# CPU.net
KiCad netlist of a schematic drawn in Altium Designer
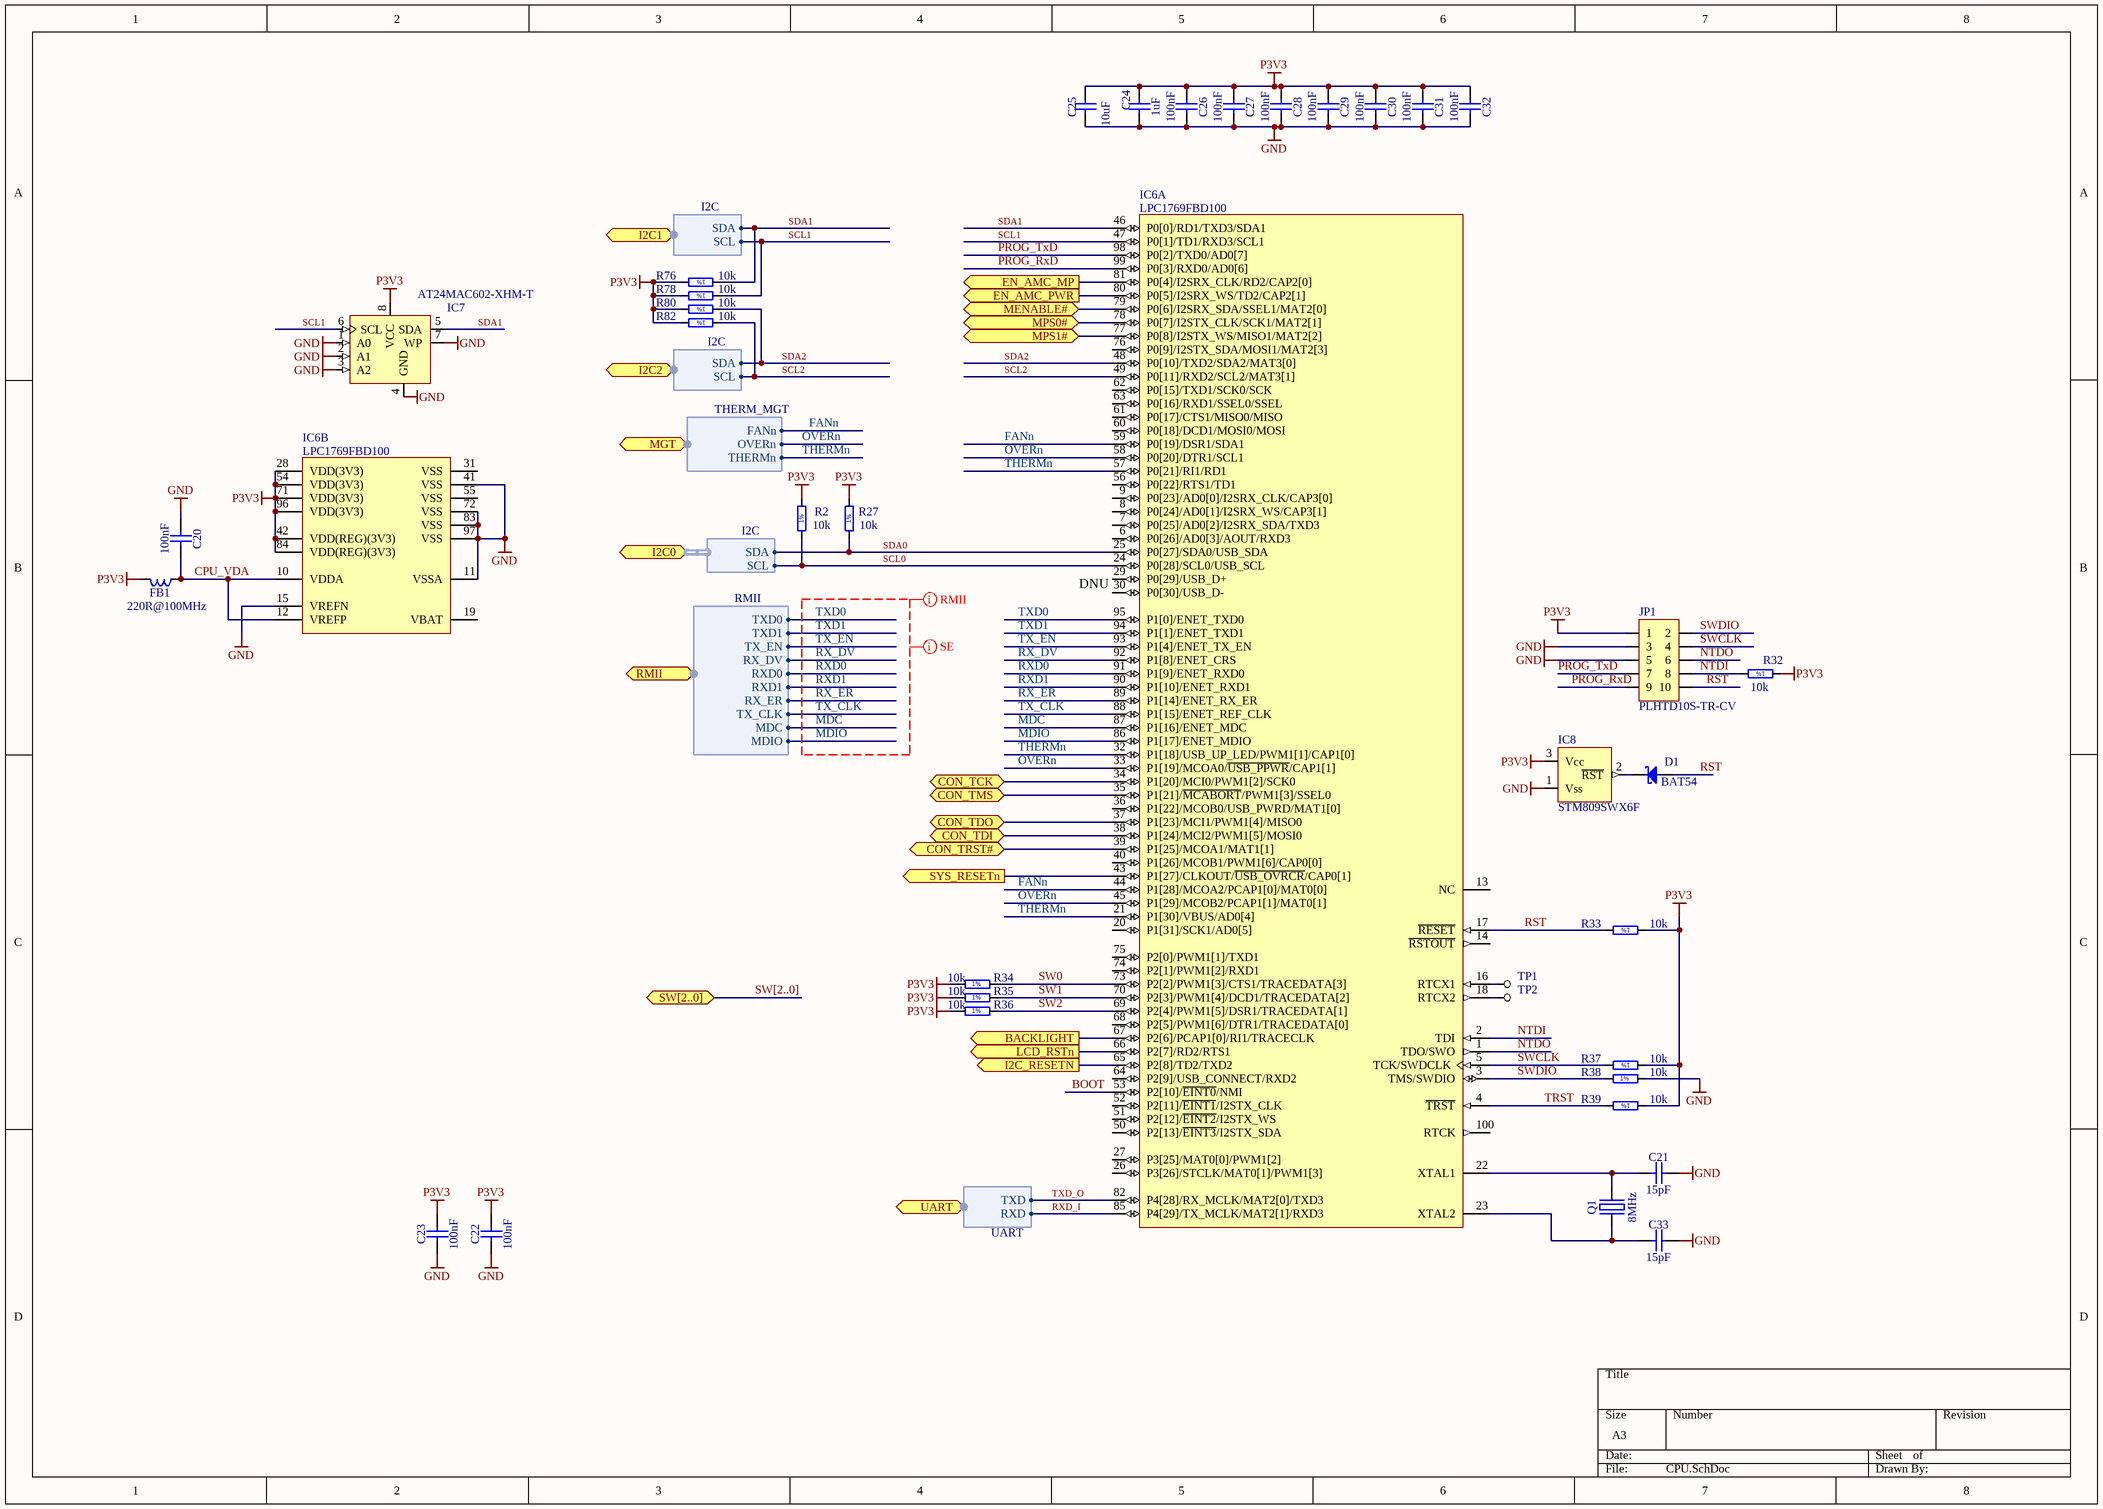
[diagram p0: CPU.SchDoc]

(export (version "E")
  (design (tool "Eeschema 10.0.6"))
  (components
    (comp (ref "C20")
      (value "100nF")
      (footprint "CAPC1005X55N")
      (description "Non-polarised capacitor")
      (fields
        (field (name "PART NUMBER") "CC0402_100NF_16V_10%_X5R")
        (field (name "VOLTAGE") "16V")
        (field (name "AUTHOR") "CERN DEM JLC")
      )
      (libsource (lib "Capacitors") (part "Capacitor - non polarized"))
    )
    (comp (ref "C21")
      (value "15pF")
      (footprint "CAPC1005X55N")
      (description "Non-polarised capacitor")
      (fields
        (field (name "PART NUMBER") "CC0402_15PF_50V_5%_C0G")
        (field (name "VOLTAGE") "50V")
        (field (name "AUTHOR") "CERN DEM JLC")
      )
      (libsource (lib "Capacitors") (part "Capacitor - non polarized"))
    )
    (comp (ref "C22")
      (value "100nF")
      (footprint "CAPC1005X55N")
      (description "Non-polarised capacitor")
      (fields
        (field (name "PART NUMBER") "CC0402_100NF_16V_10%_X5R")
        (field (name "VOLTAGE") "16V")
        (field (name "AUTHOR") "CERN DEM JLC")
      )
      (libsource (lib "Capacitors") (part "Capacitor - non polarized"))
    )
    (comp (ref "C23")
      (value "100nF")
      (footprint "CAPC1005X55N")
      (description "Non-polarised capacitor")
      (fields
        (field (name "PART NUMBER") "CC0402_100NF_16V_10%_X5R")
        (field (name "VOLTAGE") "16V")
        (field (name "AUTHOR") "CERN DEM JLC")
      )
      (libsource (lib "Capacitors") (part "Capacitor - non polarized"))
    )
    (comp (ref "C24")
      (value "1uF")
      (footprint "CAPC1608X87N")
      (description "Non-polarised capacitor")
      (fields
        (field (name "PART NUMBER") "CC0603_1UF_25V_10%_X7R")
        (field (name "VOLTAGE") "25V")
        (field (name "AUTHOR") "CERN DEM JLC")
      )
      (libsource (lib "Capacitors") (part "Capacitor - non polarized"))
    )
    (comp (ref "C25")
      (value "10uF")
      (footprint "CAPC2012X135N")
      (description "Non-polarised capacitor")
      (fields
        (field (name "PART NUMBER") "CC0805_10UF_10V_10%_X7R")
        (field (name "VOLTAGE") "10V")
        (field (name "AUTHOR") "CERN DEM JLC")
      )
      (libsource (lib "Capacitors") (part "Capacitor - non polarized"))
    )
    (comp (ref "C26")
      (value "100nF")
      (footprint "CAPC1005X55N")
      (description "Non-polarised capacitor")
      (fields
        (field (name "PART NUMBER") "CC0402_100NF_16V_10%_X5R")
        (field (name "VOLTAGE") "16V")
        (field (name "AUTHOR") "CERN DEM JLC")
      )
      (libsource (lib "Capacitors") (part "Capacitor - non polarized"))
    )
    (comp (ref "C27")
      (value "100nF")
      (footprint "CAPC1005X55N")
      (description "Non-polarised capacitor")
      (fields
        (field (name "PART NUMBER") "CC0402_100NF_16V_10%_X5R")
        (field (name "VOLTAGE") "16V")
        (field (name "AUTHOR") "CERN DEM JLC")
      )
      (libsource (lib "Capacitors") (part "Capacitor - non polarized"))
    )
    (comp (ref "C28")
      (value "100nF")
      (footprint "CAPC1005X55N")
      (description "Non-polarised capacitor")
      (fields
        (field (name "PART NUMBER") "CC0402_100NF_16V_10%_X5R")
        (field (name "VOLTAGE") "16V")
        (field (name "AUTHOR") "CERN DEM JLC")
      )
      (libsource (lib "Capacitors") (part "Capacitor - non polarized"))
    )
    (comp (ref "C29")
      (value "100nF")
      (footprint "CAPC1005X55N")
      (description "Non-polarised capacitor")
      (fields
        (field (name "PART NUMBER") "CC0402_100NF_16V_10%_X5R")
        (field (name "VOLTAGE") "16V")
        (field (name "AUTHOR") "CERN DEM JLC")
      )
      (libsource (lib "Capacitors") (part "Capacitor - non polarized"))
    )
    (comp (ref "C30")
      (value "100nF")
      (footprint "CAPC1005X55N")
      (description "Non-polarised capacitor")
      (fields
        (field (name "PART NUMBER") "CC0402_100NF_16V_10%_X5R")
        (field (name "VOLTAGE") "16V")
        (field (name "AUTHOR") "CERN DEM JLC")
      )
      (libsource (lib "Capacitors") (part "Capacitor - non polarized"))
    )
    (comp (ref "C31")
      (value "100nF")
      (footprint "CAPC1005X55N")
      (description "Non-polarised capacitor")
      (fields
        (field (name "PART NUMBER") "CC0402_100NF_16V_10%_X5R")
        (field (name "VOLTAGE") "16V")
        (field (name "AUTHOR") "CERN DEM JLC")
      )
      (libsource (lib "Capacitors") (part "Capacitor - non polarized"))
    )
    (comp (ref "C32")
      (value "100nF")
      (footprint "CAPC1005X55N")
      (description "Non-polarised capacitor")
      (fields
        (field (name "PART NUMBER") "CC0402_100NF_16V_10%_X5R")
        (field (name "VOLTAGE") "16V")
        (field (name "AUTHOR") "CERN DEM JLC")
      )
      (libsource (lib "Capacitors") (part "Capacitor - non polarized"))
    )
    (comp (ref "C33")
      (value "15pF")
      (footprint "CAPC1005X55N")
      (description "Non-polarised capacitor")
      (fields
        (field (name "PART NUMBER") "CC0402_15PF_50V_5%_C0G")
        (field (name "VOLTAGE") "50V")
        (field (name "AUTHOR") "CERN DEM JLC")
      )
      (libsource (lib "Capacitors") (part "Capacitor - non polarized"))
    )
    (comp (ref "D1")
      (value "BAT54")
      (footprint "SOT95P240X130-3N")
      (description "Diode Schottky  Anode Pin 1 Cathode Pin 3 (Pas de pin 2)")
      (fields
        (field (name "VOLTAGE") "30V")
        (field (name "POWER") "200mA")
        (field (name "AUTHOR") "CERN DEM JLC")
      )
      (libsource (lib "ICs And Semiconductors") (part "Diode Schottky A1C3"))
    )
    (comp (ref "FB1")
      (value "220R@100MHz")
      (footprint "INDC2012X105N")
      (description "Inductor")
      (fields
        (field (name "PART NUMBER") "IND0805_MURATA_BLM21PG221SN1D")
        (field (name "POWER") "2A")
        (field (name "AUTHOR") "CERN DEM JLC")
      )
      (libsource (lib "Inductors & Transformers") (part "Inductor"))
    )
    (comp (ref "IC6")
      (value "LPC1769FBD100")
      (footprint "QFP50P1600X1600X160-100N")
      (description "LPC1768 Series 64kB 120MHz 32-Bit ARM Cortex-M3 Microcontroller")
      (fields (field (name "MANUFACTURER") "NXP SEMICONDUCTORS") (field (name "AUTHOR") "CERN DEM JLC"))
      (libsource (lib "ICs And Semiconductors") (part "LPC1769FBD100"))
    )
    (comp (ref "IC7")
      (value "AT24MAC602-XHM-T")
      (footprint "TSSOP-8")
      (description "Serial 2K EEPROM+ 48bit MAC")
      (libsource (lib "LIBRARY_SCH") (part "MEM_24MAC602"))
    )
    (comp (ref "IC8")
      (value "STM809SWX6F")
      (footprint "SOT-23")
      (description "2.93V  Reset circuit")
      (libsource (lib "LIBRARY_SCH") (part "VMON_STM809"))
    )
    (comp (ref "JP1")
      (value "PLHTD10S-TR-CV")
      (footprint "PLHTD10S-TR-CV")
      (description "1.27 mm dual row goldpin (Maritex)")
      (libsource (lib "LIBRARY_SCH") (part "CON_2x5 1.27 SMT Male"))
    )
    (comp (ref "Q1")
      (value "8MHz")
      (footprint "XTAL_TXC_7A")
      (description "Quartz Crystal")
      (fields
        (field (name "PART NUMBER") "XTAL_8MHZ_TXC_7A-8.000MAAE-T")
        (field (name "MANUFACTURER") "TXC CORPORATION")
        (field (name "AUTHOR") "CERN DEM JLC")
      )
      (libsource (lib "ICs And Semiconductors") (part "Quartz Crystal"))
    )
    (comp (ref "R2")
      (value "10k")
      (footprint "RESC1005X40N")
      (description "Resistor - 1%")
      (fields
        (field (name "PART NUMBER") "R0402_10K_1%_0.0625W_100PPM")
        (field (name "POWER") "0.0625W")
        (field (name "AUTHOR") "CERN DEM JLC")
      )
      (libsource (lib "Resistors") (part "Resistor - 1%"))
    )
    (comp (ref "R27")
      (value "10k")
      (footprint "RESC1005X40N")
      (description "Resistor - 1%")
      (fields
        (field (name "PART NUMBER") "R0402_10K_1%_0.0625W_100PPM")
        (field (name "POWER") "0.0625W")
        (field (name "AUTHOR") "CERN DEM JLC")
      )
      (libsource (lib "Resistors") (part "Resistor - 1%"))
    )
    (comp (ref "R32")
      (value "10k")
      (footprint "RESC1005X40N")
      (description "Resistor - 1%")
      (fields
        (field (name "PART NUMBER") "R0402_10K_1%_0.0625W_100PPM")
        (field (name "POWER") "0.0625W")
        (field (name "AUTHOR") "CERN DEM JLC")
      )
      (libsource (lib "Resistors") (part "Resistor - 1%"))
    )
    (comp (ref "R33")
      (value "10k")
      (footprint "RESC1005X40N")
      (description "Resistor - 1%")
      (fields
        (field (name "PART NUMBER") "R0402_10K_1%_0.0625W_100PPM")
        (field (name "POWER") "0.0625W")
        (field (name "AUTHOR") "CERN DEM JLC")
      )
      (libsource (lib "Resistors") (part "Resistor - 1%"))
    )
    (comp (ref "R34")
      (value "10k")
      (footprint "RESC1005X40N")
      (description "Resistor - 1%")
      (fields
        (field (name "PART NUMBER") "R0402_10K_1%_0.0625W_100PPM")
        (field (name "POWER") "0.0625W")
        (field (name "AUTHOR") "CERN DEM JLC")
      )
      (libsource (lib "Resistors") (part "Resistor - 1%"))
    )
    (comp (ref "R35")
      (value "10k")
      (footprint "RESC1005X40N")
      (description "Resistor - 1%")
      (fields
        (field (name "PART NUMBER") "R0402_10K_1%_0.0625W_100PPM")
        (field (name "POWER") "0.0625W")
        (field (name "AUTHOR") "CERN DEM JLC")
      )
      (libsource (lib "Resistors") (part "Resistor - 1%"))
    )
    (comp (ref "R36")
      (value "10k")
      (footprint "RESC1005X40N")
      (description "Resistor - 1%")
      (fields
        (field (name "PART NUMBER") "R0402_10K_1%_0.0625W_100PPM")
        (field (name "POWER") "0.0625W")
        (field (name "AUTHOR") "CERN DEM JLC")
      )
      (libsource (lib "Resistors") (part "Resistor - 1%"))
    )
    (comp (ref "R37")
      (value "10k")
      (footprint "RESC1005X40N")
      (description "Resistor - 1%")
      (fields
        (field (name "PART NUMBER") "R0402_10K_1%_0.0625W_100PPM")
        (field (name "POWER") "0.0625W")
        (field (name "AUTHOR") "CERN DEM JLC")
      )
      (libsource (lib "Resistors") (part "Resistor - 1%"))
    )
    (comp (ref "R38")
      (value "10k")
      (footprint "RESC1005X40N")
      (description "Resistor - 1%")
      (fields
        (field (name "PART NUMBER") "R0402_10K_1%_0.0625W_100PPM")
        (field (name "POWER") "0.0625W")
        (field (name "AUTHOR") "CERN DEM JLC")
      )
      (libsource (lib "Resistors") (part "Resistor - 1%"))
    )
    (comp (ref "R39")
      (value "10k")
      (footprint "RESC1005X40N")
      (description "Resistor - 1%")
      (fields
        (field (name "PART NUMBER") "R0402_10K_1%_0.0625W_100PPM")
        (field (name "POWER") "0.0625W")
        (field (name "AUTHOR") "CERN DEM JLC")
      )
      (libsource (lib "Resistors") (part "Resistor - 1%"))
    )
    (comp (ref "R76")
      (value "10k")
      (footprint "RESC1005X40N")
      (description "Resistor - 1%")
      (fields
        (field (name "PART NUMBER") "R0402_10K_1%_0.0625W_100PPM")
        (field (name "POWER") "0.0625W")
        (field (name "AUTHOR") "CERN DEM JLC")
      )
      (libsource (lib "Resistors") (part "Resistor - 1%"))
    )
    (comp (ref "R78")
      (value "10k")
      (footprint "RESC1005X40N")
      (description "Resistor - 1%")
      (fields
        (field (name "PART NUMBER") "R0402_10K_1%_0.0625W_100PPM")
        (field (name "POWER") "0.0625W")
        (field (name "AUTHOR") "CERN DEM JLC")
      )
      (libsource (lib "Resistors") (part "Resistor - 1%"))
    )
    (comp (ref "R80")
      (value "10k")
      (footprint "RESC1005X40N")
      (description "Resistor - 1%")
      (fields
        (field (name "PART NUMBER") "R0402_10K_1%_0.0625W_100PPM")
        (field (name "POWER") "0.0625W")
        (field (name "AUTHOR") "CERN DEM JLC")
      )
      (libsource (lib "Resistors") (part "Resistor - 1%"))
    )
    (comp (ref "R82")
      (value "10k")
      (footprint "RESC1005X40N")
      (description "Resistor - 1%")
      (fields
        (field (name "PART NUMBER") "R0402_10K_1%_0.0625W_100PPM")
        (field (name "POWER") "0.0625W")
        (field (name "AUTHOR") "CERN DEM JLC")
      )
      (libsource (lib "Resistors") (part "Resistor - 1%"))
    )
    (comp (ref "TP1")
      (value "TP")
      (footprint "TP")
      (description "Testpoint")
      (libsource (lib "LIBRARY_SCH") (part "TP"))
    )
    (comp (ref "TP2")
      (value "TP")
      (footprint "TP")
      (description "Testpoint")
      (libsource (lib "LIBRARY_SCH") (part "TP"))
    )
  )
  (nets
    (net (code "5") (name "/BACKLIGHT") (class "Default")
      (node (ref "IC6") (pin "67") (pinfunction "P2[6]/PCAP1[0]/RI1/TRACECLK_67") (pintype "bidirectional"))
    )
    (net (code "6") (name "/BOOT") (class "Default")
      (node (ref "IC6") (pin "53") (pinfunction "P2[10]/~{EINT0}/NMI_53") (pintype "bidirectional"))
    )
    (net (code "7") (name "/CON_TCK") (class "Default")
      (node (ref "IC6") (pin "34") (pinfunction "P1[20]/MCI0/PWM1[2]/SCK0_34") (pintype "bidirectional"))
    )
    (net (code "8") (name "/CON_TDI") (class "Default")
      (node (ref "IC6") (pin "38") (pinfunction "P1[24]/MCI2/PWM1[5]/MOSI0_38") (pintype "bidirectional"))
    )
    (net (code "9") (name "/CON_TDO") (class "Default")
      (node (ref "IC6") (pin "37") (pinfunction "P1[23]/MCI1/PWM1[4]/MISO0_37") (pintype "bidirectional"))
    )
    (net (code "10") (name "/CON_TMS") (class "Default")
      (node (ref "IC6") (pin "35") (pinfunction "P1[21]/~{MCABORT}/PWM1[3]/SSEL0_35") (pintype "bidirectional"))
    )
    (net (code "11") (name "/CON_TRST#") (class "Default")
      (node (ref "IC6") (pin "39") (pinfunction "P1[25]/MCOA1/MAT1[1]_39") (pintype "bidirectional"))
    )
    (net (code "12") (name "/CPU_VDA") (class "Default")
      (node (ref "C20") (pin "2") (pinfunction "2_2") (pintype "passive"))
      (node (ref "FB1") (pin "1") (pinfunction "1_1") (pintype "passive"))
      (node (ref "IC6") (pin "10") (pinfunction "VDDA_10") (pintype "power_in"))
      (node (ref "IC6") (pin "12") (pinfunction "VREFP_12") (pintype "power_in"))
    )
    (net (code "13") (name "/EN_AMC_MP") (class "Default")
      (node (ref "IC6") (pin "81") (pinfunction "P0[4]/I2SRX_CLK/RD2/CAP2[0]_81") (pintype "bidirectional"))
    )
    (net (code "14") (name "/EN_AMC_PWR") (class "Default")
      (node (ref "IC6") (pin "80") (pinfunction "P0[5]/I2SRX_WS/TD2/CAP2[1]_80") (pintype "bidirectional"))
    )
    (net (code "15") (name "/FANn") (class "Default")
      (node (ref "IC6") (pin "44") (pinfunction "P1[28]/MCOA2/PCAP1[0]/MAT0[0]_44") (pintype "bidirectional"))
      (node (ref "IC6") (pin "59") (pinfunction "P0[19]/DSR1/SDA1_59") (pintype "bidirectional"))
    )
    (net (code "16") (name "/I2C_RESETN") (class "Default")
      (node (ref "IC6") (pin "65") (pinfunction "P2[8]/TD2/TXD2_65") (pintype "bidirectional"))
    )
    (net (code "17") (name "/LCD_RSTn") (class "Default")
      (node (ref "IC6") (pin "66") (pinfunction "P2[7]/RD2/RTS1_66") (pintype "bidirectional"))
    )
    (net (code "18") (name "/MDC") (class "Default")
      (node (ref "IC6") (pin "87") (pinfunction "P1[16]/ENET_MDC_87") (pintype "bidirectional"))
    )
    (net (code "19") (name "/MDIO") (class "Default")
      (node (ref "IC6") (pin "86") (pinfunction "P1[17]/ENET_MDIO_86") (pintype "bidirectional"))
    )
    (net (code "20") (name "/MENABLE#") (class "Default")
      (node (ref "IC6") (pin "79") (pinfunction "P0[6]/I2SRX_SDA/SSEL1/MAT2[0]_79") (pintype "bidirectional"))
    )
    (net (code "21") (name "/MPS0#") (class "Default")
      (node (ref "IC6") (pin "78") (pinfunction "P0[7]/I2STX_CLK/SCK1/MAT2[1]_78") (pintype "bidirectional"))
    )
    (net (code "22") (name "/MPS1#") (class "Default")
      (node (ref "IC6") (pin "77") (pinfunction "P0[8]/I2STX_WS/MISO1/MAT2[2]_77") (pintype "bidirectional"))
    )
    (net (code "23") (name "/NTDI") (class "Default")
      (node (ref "IC6") (pin "2") (pinfunction "TDI_2") (pintype "input"))
      (node (ref "JP1") (pin "8") (pinfunction "8_8") (pintype "passive"))
      (node (ref "R32") (pin "2") (pinfunction "2_2") (pintype "passive"))
    )
    (net (code "24") (name "/NTDO") (class "Default")
      (node (ref "IC6") (pin "1") (pinfunction "TDO/SWO_1") (pintype "output"))
      (node (ref "JP1") (pin "6") (pinfunction "6_6") (pintype "passive"))
    )
    (net (code "25") (name "/OVERn") (class "Default")
      (node (ref "IC6") (pin "33") (pinfunction "P1[19]/MCOA0/~{USB_PPWR}/CAP1[1]_33") (pintype "bidirectional"))
      (node (ref "IC6") (pin "45") (pinfunction "P1[29]/MCOB2/PCAP1[1]/MAT0[1]_45") (pintype "bidirectional"))
      (node (ref "IC6") (pin "58") (pinfunction "P0[20]/DTR1/SCL1_58") (pintype "bidirectional"))
    )
    (net (code "26") (name "/PROG_RxD") (class "Default")
      (node (ref "IC6") (pin "99") (pinfunction "P0[3]/RXD0/AD0[6]_99") (pintype "bidirectional"))
      (node (ref "JP1") (pin "9") (pinfunction "9_9") (pintype "passive"))
    )
    (net (code "27") (name "/PROG_TxD") (class "Default")
      (node (ref "IC6") (pin "98") (pinfunction "P0[2]/TXD0/AD0[7]_98") (pintype "bidirectional"))
      (node (ref "JP1") (pin "7") (pinfunction "7_7") (pintype "passive"))
    )
    (net (code "28") (name "/RST") (class "Default")
      (node (ref "D1") (pin "1") (pinfunction "A_1") (pintype "passive"))
      (node (ref "IC6") (pin "17") (pinfunction "~{RESET}_17") (pintype "input"))
      (node (ref "JP1") (pin "10") (pinfunction "10_10") (pintype "passive"))
      (node (ref "R33") (pin "2") (pinfunction "2_2") (pintype "passive"))
    )
    (net (code "29") (name "/RXD0") (class "Default")
      (node (ref "IC6") (pin "91") (pinfunction "P1[9]/ENET_RXD0_91") (pintype "bidirectional"))
    )
    (net (code "30") (name "/RXD1") (class "Default")
      (node (ref "IC6") (pin "90") (pinfunction "P1[10]/ENET_RXD1_90") (pintype "bidirectional"))
    )
    (net (code "31") (name "/RXD_I") (class "Default")
      (node (ref "IC6") (pin "85") (pinfunction "P4[29]/TX_MCLK/MAT2[1]/RXD3_85") (pintype "bidirectional"))
    )
    (net (code "32") (name "/RX_DV") (class "Default")
      (node (ref "IC6") (pin "92") (pinfunction "P1[8]/ENET_CRS_92") (pintype "bidirectional"))
    )
    (net (code "33") (name "/RX_ER") (class "Default")
      (node (ref "IC6") (pin "89") (pinfunction "P1[14]/ENET_RX_ER_89") (pintype "bidirectional"))
    )
    (net (code "34") (name "/SCL0") (class "Default")
      (node (ref "IC6") (pin "24") (pinfunction "P0[28]/SCL0/USB_SCL_24") (pintype "bidirectional"))
      (node (ref "R2") (pin "1") (pinfunction "1_1") (pintype "passive"))
    )
    (net (code "35") (name "/SCL1") (class "Default")
      (node (ref "IC6") (pin "47") (pinfunction "P0[1]/TD1/RXD3/SCL1_47") (pintype "bidirectional"))
      (node (ref "IC7") (pin "6") (pinfunction "SCL_6") (pintype "input"))
      (node (ref "R78") (pin "1") (pinfunction "1_1") (pintype "passive"))
    )
    (net (code "36") (name "/SCL2") (class "Default")
      (node (ref "IC6") (pin "49") (pinfunction "P0[11]/RXD2/SCL2/MAT3[1]_49") (pintype "bidirectional"))
      (node (ref "R82") (pin "1") (pinfunction "1_1") (pintype "passive"))
    )
    (net (code "37") (name "/SDA0") (class "Default")
      (node (ref "IC6") (pin "25") (pinfunction "P0[27]/SDA0/USB_SDA_25") (pintype "bidirectional"))
      (node (ref "R27") (pin "1") (pinfunction "1_1") (pintype "passive"))
    )
    (net (code "38") (name "/SDA1") (class "Default")
      (node (ref "IC6") (pin "46") (pinfunction "P0[0]/RD1/TXD3/SDA1_46") (pintype "bidirectional"))
      (node (ref "IC7") (pin "5") (pinfunction "SDA_5") (pintype "bidirectional"))
      (node (ref "R76") (pin "1") (pinfunction "1_1") (pintype "passive"))
    )
    (net (code "39") (name "/SDA2") (class "Default")
      (node (ref "IC6") (pin "48") (pinfunction "P0[10]/TXD2/SDA2/MAT3[0]_48") (pintype "bidirectional"))
      (node (ref "R80") (pin "1") (pinfunction "1_1") (pintype "passive"))
    )
    (net (code "40") (name "/SW0") (class "Default")
      (node (ref "IC6") (pin "73") (pinfunction "P2[2]/PWM1[3]/CTS1/TRACEDATA[3]_73") (pintype "bidirectional"))
      (node (ref "R34") (pin "2") (pinfunction "2_2") (pintype "passive"))
    )
    (net (code "41") (name "/SW1") (class "Default")
      (node (ref "IC6") (pin "70") (pinfunction "P2[3]/PWM1[4]/DCD1/TRACEDATA[2]_70") (pintype "bidirectional"))
      (node (ref "R35") (pin "2") (pinfunction "2_2") (pintype "passive"))
    )
    (net (code "42") (name "/SW2") (class "Default")
      (node (ref "IC6") (pin "69") (pinfunction "P2[4]/PWM1[5]/DSR1/TRACEDATA[1]_69") (pintype "bidirectional"))
      (node (ref "R36") (pin "2") (pinfunction "2_2") (pintype "passive"))
    )
    (net (code "43") (name "/SWCLK") (class "Default")
      (node (ref "IC6") (pin "5") (pinfunction "TCK/SWDCLK_5") (pintype "input"))
      (node (ref "JP1") (pin "4") (pinfunction "4_4") (pintype "passive"))
      (node (ref "R37") (pin "2") (pinfunction "2_2") (pintype "passive"))
    )
    (net (code "44") (name "/SWDIO") (class "Default")
      (node (ref "IC6") (pin "3") (pinfunction "TMS/SWDIO_3") (pintype "bidirectional"))
      (node (ref "JP1") (pin "2") (pinfunction "2_2") (pintype "passive"))
      (node (ref "R38") (pin "1") (pinfunction "1_1") (pintype "passive"))
    )
    (net (code "46") (name "/SYS_RESETn") (class "Default")
      (node (ref "IC6") (pin "43") (pinfunction "P1[27]/CLKOUT/~{USB_OVRCR}/CAP0[1]_43") (pintype "bidirectional"))
    )
    (net (code "47") (name "/THERMn") (class "Default")
      (node (ref "IC6") (pin "21") (pinfunction "P1[30]/VBUS/AD0[4]_21") (pintype "bidirectional"))
      (node (ref "IC6") (pin "32") (pinfunction "P1[18]/USB_UP_LED/PWM1[1]/CAP1[0]_32") (pintype "bidirectional"))
      (node (ref "IC6") (pin "57") (pinfunction "P0[21]/RI1/RD1_57") (pintype "bidirectional"))
    )
    (net (code "48") (name "/TRST") (class "Default")
      (node (ref "IC6") (pin "4") (pinfunction "~{TRST}_4") (pintype "input"))
      (node (ref "R39") (pin "2") (pinfunction "2_2") (pintype "passive"))
    )
    (net (code "49") (name "/TXD0") (class "Default")
      (node (ref "IC6") (pin "95") (pinfunction "P1[0]/ENET_TXD0_95") (pintype "bidirectional"))
    )
    (net (code "50") (name "/TXD1") (class "Default")
      (node (ref "IC6") (pin "94") (pinfunction "P1[1]/ENET_TXD1_94") (pintype "bidirectional"))
    )
    (net (code "51") (name "/TXD_O") (class "Default")
      (node (ref "IC6") (pin "82") (pinfunction "P4[28]/RX_MCLK/MAT2[0]/TXD3_82") (pintype "bidirectional"))
    )
    (net (code "52") (name "/TX_CLK") (class "Default")
      (node (ref "IC6") (pin "88") (pinfunction "P1[15]/ENET_REF_CLK_88") (pintype "bidirectional"))
    )
    (net (code "53") (name "/TX_EN") (class "Default")
      (node (ref "IC6") (pin "93") (pinfunction "P1[4]/ENET_TX_EN_93") (pintype "bidirectional"))
    )
    (net (code "58") (name "GND") (class "Default")
      (node (ref "C20") (pin "1") (pinfunction "1_1") (pintype "passive"))
      (node (ref "C21") (pin "2") (pinfunction "2_2") (pintype "passive"))
      (node (ref "C22") (pin "1") (pinfunction "1_1") (pintype "passive"))
      (node (ref "C23") (pin "1") (pinfunction "1_1") (pintype "passive"))
      (node (ref "C24") (pin "1") (pinfunction "1_1") (pintype "passive"))
      (node (ref "C25") (pin "2") (pinfunction "2_2") (pintype "passive"))
      (node (ref "C26") (pin "1") (pinfunction "1_1") (pintype "passive"))
      (node (ref "C27") (pin "1") (pinfunction "1_1") (pintype "passive"))
      (node (ref "C28") (pin "1") (pinfunction "1_1") (pintype "passive"))
      (node (ref "C29") (pin "1") (pinfunction "1_1") (pintype "passive"))
      (node (ref "C30") (pin "1") (pinfunction "1_1") (pintype "passive"))
      (node (ref "C31") (pin "1") (pinfunction "1_1") (pintype "passive"))
      (node (ref "C32") (pin "1") (pinfunction "1_1") (pintype "passive"))
      (node (ref "C33") (pin "2") (pinfunction "2_2") (pintype "passive"))
      (node (ref "IC6") (pin "11") (pinfunction "VSSA_11") (pintype "power_in"))
      (node (ref "IC6") (pin "15") (pinfunction "VREFN_15") (pintype "power_in"))
      (node (ref "IC6") (pin "41") (pinfunction "VSS_41") (pintype "power_in"))
      (node (ref "IC6") (pin "72") (pinfunction "VSS_72") (pintype "power_in"))
      (node (ref "IC6") (pin "83") (pinfunction "VSS_83") (pintype "power_in"))
      (node (ref "IC6") (pin "97") (pinfunction "VSS_97") (pintype "power_in"))
      (node (ref "IC7") (pin "1") (pinfunction "A0_1") (pintype "input"))
      (node (ref "IC7") (pin "2") (pinfunction "A1_2") (pintype "input"))
      (node (ref "IC7") (pin "3") (pinfunction "A2_3") (pintype "input"))
      (node (ref "IC7") (pin "4") (pinfunction "GND_4") (pintype "power_in"))
      (node (ref "IC7") (pin "7") (pinfunction "WP_7") (pintype "passive"))
      (node (ref "IC8") (pin "1") (pinfunction "Vss_1") (pintype "power_in"))
      (node (ref "JP1") (pin "3") (pinfunction "3_3") (pintype "passive"))
      (node (ref "JP1") (pin "5") (pinfunction "5_5") (pintype "passive"))
      (node (ref "R38") (pin "2") (pinfunction "2_2") (pintype "passive"))
    )
    (net (code "59") (name "Net-(D1-C)") (class "Default")
      (node (ref "D1") (pin "3") (pinfunction "C_3") (pintype "passive"))
      (node (ref "IC8") (pin "2") (pinfunction "~{RST}_2") (pintype "output"))
    )
    (net (code "60") (name "Net-(IC6A-RTCX1)") (class "Default")
      (node (ref "IC6") (pin "16") (pinfunction "RTCX1_16") (pintype "input"))
      (node (ref "TP1") (pin "1") (pintype "passive"))
    )
    (net (code "61") (name "Net-(IC6A-RTCX2)") (class "Default")
      (node (ref "IC6") (pin "18") (pinfunction "RTCX2_18") (pintype "output"))
      (node (ref "TP2") (pin "1") (pintype "passive"))
    )
    (net (code "62") (name "Net-(IC6A-XTAL1)") (class "Default")
      (node (ref "C21") (pin "1") (pinfunction "1_1") (pintype "passive"))
      (node (ref "IC6") (pin "22") (pinfunction "XTAL1_22") (pintype "passive"))
      (node (ref "Q1") (pin "2") (pinfunction "OSC2_2") (pintype "passive"))
    )
    (net (code "63") (name "Net-(IC6A-XTAL2)") (class "Default")
      (node (ref "C33") (pin "1") (pinfunction "1_1") (pintype "passive"))
      (node (ref "IC6") (pin "23") (pinfunction "XTAL2_23") (pintype "passive"))
      (node (ref "Q1") (pin "1") (pinfunction "OSC1_1") (pintype "passive"))
    )
    (net (code "64") (name "P3V3") (class "Default")
      (node (ref "C22") (pin "2") (pinfunction "2_2") (pintype "passive"))
      (node (ref "C23") (pin "2") (pinfunction "2_2") (pintype "passive"))
      (node (ref "C24") (pin "2") (pinfunction "2_2") (pintype "passive"))
      (node (ref "C25") (pin "1") (pinfunction "1_1") (pintype "passive"))
      (node (ref "C26") (pin "2") (pinfunction "2_2") (pintype "passive"))
      (node (ref "C27") (pin "2") (pinfunction "2_2") (pintype "passive"))
      (node (ref "C28") (pin "2") (pinfunction "2_2") (pintype "passive"))
      (node (ref "C29") (pin "2") (pinfunction "2_2") (pintype "passive"))
      (node (ref "C30") (pin "2") (pinfunction "2_2") (pintype "passive"))
      (node (ref "C31") (pin "2") (pinfunction "2_2") (pintype "passive"))
      (node (ref "C32") (pin "2") (pinfunction "2_2") (pintype "passive"))
      (node (ref "FB1") (pin "2") (pinfunction "2_2") (pintype "passive"))
      (node (ref "IC6") (pin "28") (pinfunction "VDD(3V3)_28") (pintype "power_in"))
      (node (ref "IC6") (pin "42") (pinfunction "VDD(REG)(3V3)_42") (pintype "power_in"))
      (node (ref "IC6") (pin "54") (pinfunction "VDD(3V3)_54") (pintype "power_in"))
      (node (ref "IC6") (pin "71") (pinfunction "VDD(3V3)_71") (pintype "power_in"))
      (node (ref "IC6") (pin "84") (pinfunction "VDD(REG)(3V3)_84") (pintype "power_in"))
      (node (ref "IC6") (pin "96") (pinfunction "VDD(3V3)_96") (pintype "power_in"))
      (node (ref "IC7") (pin "8") (pinfunction "VCC_8") (pintype "power_in"))
      (node (ref "IC8") (pin "3") (pinfunction "Vcc_3") (pintype "power_in"))
      (node (ref "JP1") (pin "1") (pinfunction "1_1") (pintype "passive"))
      (node (ref "R2") (pin "2") (pinfunction "2_2") (pintype "passive"))
      (node (ref "R27") (pin "2") (pinfunction "2_2") (pintype "passive"))
      (node (ref "R32") (pin "1") (pinfunction "1_1") (pintype "passive"))
      (node (ref "R33") (pin "1") (pinfunction "1_1") (pintype "passive"))
      (node (ref "R34") (pin "1") (pinfunction "1_1") (pintype "passive"))
      (node (ref "R35") (pin "1") (pinfunction "1_1") (pintype "passive"))
      (node (ref "R36") (pin "1") (pinfunction "1_1") (pintype "passive"))
      (node (ref "R37") (pin "1") (pinfunction "1_1") (pintype "passive"))
      (node (ref "R39") (pin "1") (pinfunction "1_1") (pintype "passive"))
      (node (ref "R76") (pin "2") (pinfunction "2_2") (pintype "passive"))
      (node (ref "R78") (pin "2") (pinfunction "2_2") (pintype "passive"))
      (node (ref "R80") (pin "2") (pinfunction "2_2") (pintype "passive"))
      (node (ref "R82") (pin "2") (pinfunction "2_2") (pintype "passive"))
    )
    (net (code "65") (name "unconnected-(IC6A-NC-Pad13)") (class "Default")
      (node (ref "IC6") (pin "13") (pinfunction "NC_13") (pintype "passive"))
    )
    (net (code "66") (name "unconnected-(IC6A-P0[9]{slash}I2STX_SDA{slash}MOSI1{slash}MAT2[3]-Pad76)") (class "Default")
      (node (ref "IC6") (pin "76") (pinfunction "P0[9]/I2STX_SDA/MOSI1/MAT2[3]_76") (pintype "bidirectional"))
    )
    (net (code "67") (name "unconnected-(IC6A-P0[15]{slash}TXD1{slash}SCK0{slash}SCK-Pad62)") (class "Default")
      (node (ref "IC6") (pin "62") (pinfunction "P0[15]/TXD1/SCK0/SCK_62") (pintype "bidirectional"))
    )
    (net (code "68") (name "unconnected-(IC6A-P0[16]{slash}RXD1{slash}SSEL0{slash}SSEL-Pad63)") (class "Default")
      (node (ref "IC6") (pin "63") (pinfunction "P0[16]/RXD1/SSEL0/SSEL_63") (pintype "bidirectional"))
    )
    (net (code "69") (name "unconnected-(IC6A-P0[17]{slash}CTS1{slash}MISO0{slash}MISO-Pad61)") (class "Default")
      (node (ref "IC6") (pin "61") (pinfunction "P0[17]/CTS1/MISO0/MISO_61") (pintype "bidirectional"))
    )
    (net (code "70") (name "unconnected-(IC6A-P0[18]{slash}DCD1{slash}MOSI0{slash}MOSI-Pad60)") (class "Default")
      (node (ref "IC6") (pin "60") (pinfunction "P0[18]/DCD1/MOSI0/MOSI_60") (pintype "bidirectional"))
    )
    (net (code "71") (name "unconnected-(IC6A-P0[22]{slash}RTS1{slash}TD1-Pad56)") (class "Default")
      (node (ref "IC6") (pin "56") (pinfunction "P0[22]/RTS1/TD1_56") (pintype "bidirectional"))
    )
    (net (code "72") (name "unconnected-(IC6A-P0[23]{slash}AD0[0]{slash}I2SRX_CLK{slash}CAP3[0]-Pad9)") (class "Default")
      (node (ref "IC6") (pin "9") (pinfunction "P0[23]/AD0[0]/I2SRX_CLK/CAP3[0]_9") (pintype "bidirectional"))
    )
    (net (code "73") (name "unconnected-(IC6A-P0[24]{slash}AD0[1]{slash}I2SRX_WS{slash}CAP3[1]-Pad8)") (class "Default")
      (node (ref "IC6") (pin "8") (pinfunction "P0[24]/AD0[1]/I2SRX_WS/CAP3[1]_8") (pintype "bidirectional"))
    )
    (net (code "74") (name "unconnected-(IC6A-P0[25]{slash}AD0[2]{slash}I2SRX_SDA{slash}TXD3-Pad7)") (class "Default")
      (node (ref "IC6") (pin "7") (pinfunction "P0[25]/AD0[2]/I2SRX_SDA/TXD3_7") (pintype "bidirectional"))
    )
    (net (code "75") (name "unconnected-(IC6A-P0[26]{slash}AD0[3]{slash}AOUT{slash}RXD3-Pad6)") (class "Default")
      (node (ref "IC6") (pin "6") (pinfunction "P0[26]/AD0[3]/AOUT/RXD3_6") (pintype "bidirectional"))
    )
    (net (code "76") (name "unconnected-(IC6A-P0[29]{slash}USB_D+-Pad29)") (class "Default")
      (node (ref "IC6") (pin "29") (pinfunction "P0[29]/USB_D+_29") (pintype "bidirectional"))
    )
    (net (code "77") (name "unconnected-(IC6A-P0[30]{slash}USB_D--Pad30)") (class "Default")
      (node (ref "IC6") (pin "30") (pinfunction "P0[30]/USB_D-_30") (pintype "bidirectional"))
    )
    (net (code "78") (name "unconnected-(IC6A-P1[22]{slash}MCOB0{slash}USB_PWRD{slash}MAT1[0]-Pad36)") (class "Default")
      (node (ref "IC6") (pin "36") (pinfunction "P1[22]/MCOB0/USB_PWRD/MAT1[0]_36") (pintype "bidirectional"))
    )
    (net (code "79") (name "unconnected-(IC6A-P1[26]{slash}MCOB1{slash}PWM1[6]{slash}CAP0[0]-Pad40)") (class "Default")
      (node (ref "IC6") (pin "40") (pinfunction "P1[26]/MCOB1/PWM1[6]/CAP0[0]_40") (pintype "bidirectional"))
    )
    (net (code "80") (name "unconnected-(IC6A-P1[31]{slash}SCK1{slash}AD0[5]-Pad20)") (class "Default")
      (node (ref "IC6") (pin "20") (pinfunction "P1[31]/SCK1/AD0[5]_20") (pintype "bidirectional"))
    )
    (net (code "81") (name "unconnected-(IC6A-P2[0]{slash}PWM1[1]{slash}TXD1-Pad75)") (class "Default")
      (node (ref "IC6") (pin "75") (pinfunction "P2[0]/PWM1[1]/TXD1_75") (pintype "bidirectional"))
    )
    (net (code "82") (name "unconnected-(IC6A-P2[1]{slash}PWM1[2]{slash}RXD1-Pad74)") (class "Default")
      (node (ref "IC6") (pin "74") (pinfunction "P2[1]/PWM1[2]/RXD1_74") (pintype "bidirectional"))
    )
    (net (code "83") (name "unconnected-(IC6A-P2[5]{slash}PWM1[6]{slash}DTR1{slash}TRACEDATA[0]-Pad68)") (class "Default")
      (node (ref "IC6") (pin "68") (pinfunction "P2[5]/PWM1[6]/DTR1/TRACEDATA[0]_68") (pintype "bidirectional"))
    )
    (net (code "84") (name "unconnected-(IC6A-P2[9]{slash}USB_CONNECT{slash}RXD2-Pad64)") (class "Default")
      (node (ref "IC6") (pin "64") (pinfunction "P2[9]/USB_CONNECT/RXD2_64") (pintype "bidirectional"))
    )
    (net (code "85") (name "unconnected-(IC6A-P2[11]{slash}~{EINT1}{slash}I2STX_CLK-Pad52)") (class "Default")
      (node (ref "IC6") (pin "52") (pinfunction "P2[11]/~{EINT1}/I2STX_CLK_52") (pintype "bidirectional"))
    )
    (net (code "86") (name "unconnected-(IC6A-P2[12]{slash}~{EINT2}{slash}I2STX_WS-Pad51)") (class "Default")
      (node (ref "IC6") (pin "51") (pinfunction "P2[12]/~{EINT2}/I2STX_WS_51") (pintype "bidirectional"))
    )
    (net (code "87") (name "unconnected-(IC6A-P2[13]{slash}~{EINT3}{slash}I2STX_SDA-Pad50)") (class "Default")
      (node (ref "IC6") (pin "50") (pinfunction "P2[13]/~{EINT3}/I2STX_SDA_50") (pintype "bidirectional"))
    )
    (net (code "88") (name "unconnected-(IC6A-P3[25]{slash}MAT0[0]{slash}PWM1[2]-Pad27)") (class "Default")
      (node (ref "IC6") (pin "27") (pinfunction "P3[25]/MAT0[0]/PWM1[2]_27") (pintype "bidirectional"))
    )
    (net (code "89") (name "unconnected-(IC6A-P3[26]{slash}STCLK{slash}MAT0[1]{slash}PWM1[3]-Pad26)") (class "Default")
      (node (ref "IC6") (pin "26") (pinfunction "P3[26]/STCLK/MAT0[1]/PWM1[3]_26") (pintype "bidirectional"))
    )
    (net (code "90") (name "unconnected-(IC6A-RTCK-Pad100)") (class "Default")
      (node (ref "IC6") (pin "100") (pinfunction "RTCK_100") (pintype "output"))
    )
    (net (code "91") (name "unconnected-(IC6A-~{RSTOUT}-Pad14)") (class "Default")
      (node (ref "IC6") (pin "14") (pinfunction "~{RSTOUT}_14") (pintype "output"))
    )
    (net (code "92") (name "unconnected-(IC6B-VBAT-Pad19)") (class "Default")
      (node (ref "IC6") (pin "19") (pinfunction "VBAT_19") (pintype "power_in"))
    )
    (net (code "93") (name "unconnected-(IC6B-VSS-Pad31)") (class "Default")
      (node (ref "IC6") (pin "31") (pinfunction "VSS_31") (pintype "power_in"))
    )
    (net (code "94") (name "unconnected-(IC6B-VSS-Pad55)") (class "Default")
      (node (ref "IC6") (pin "55") (pinfunction "VSS_55") (pintype "power_in"))
    )
  )
)
